# SCH_Sheet-2-more_2025-10-19.net
KiCad netlist of a schematic drawn in EasyEDA
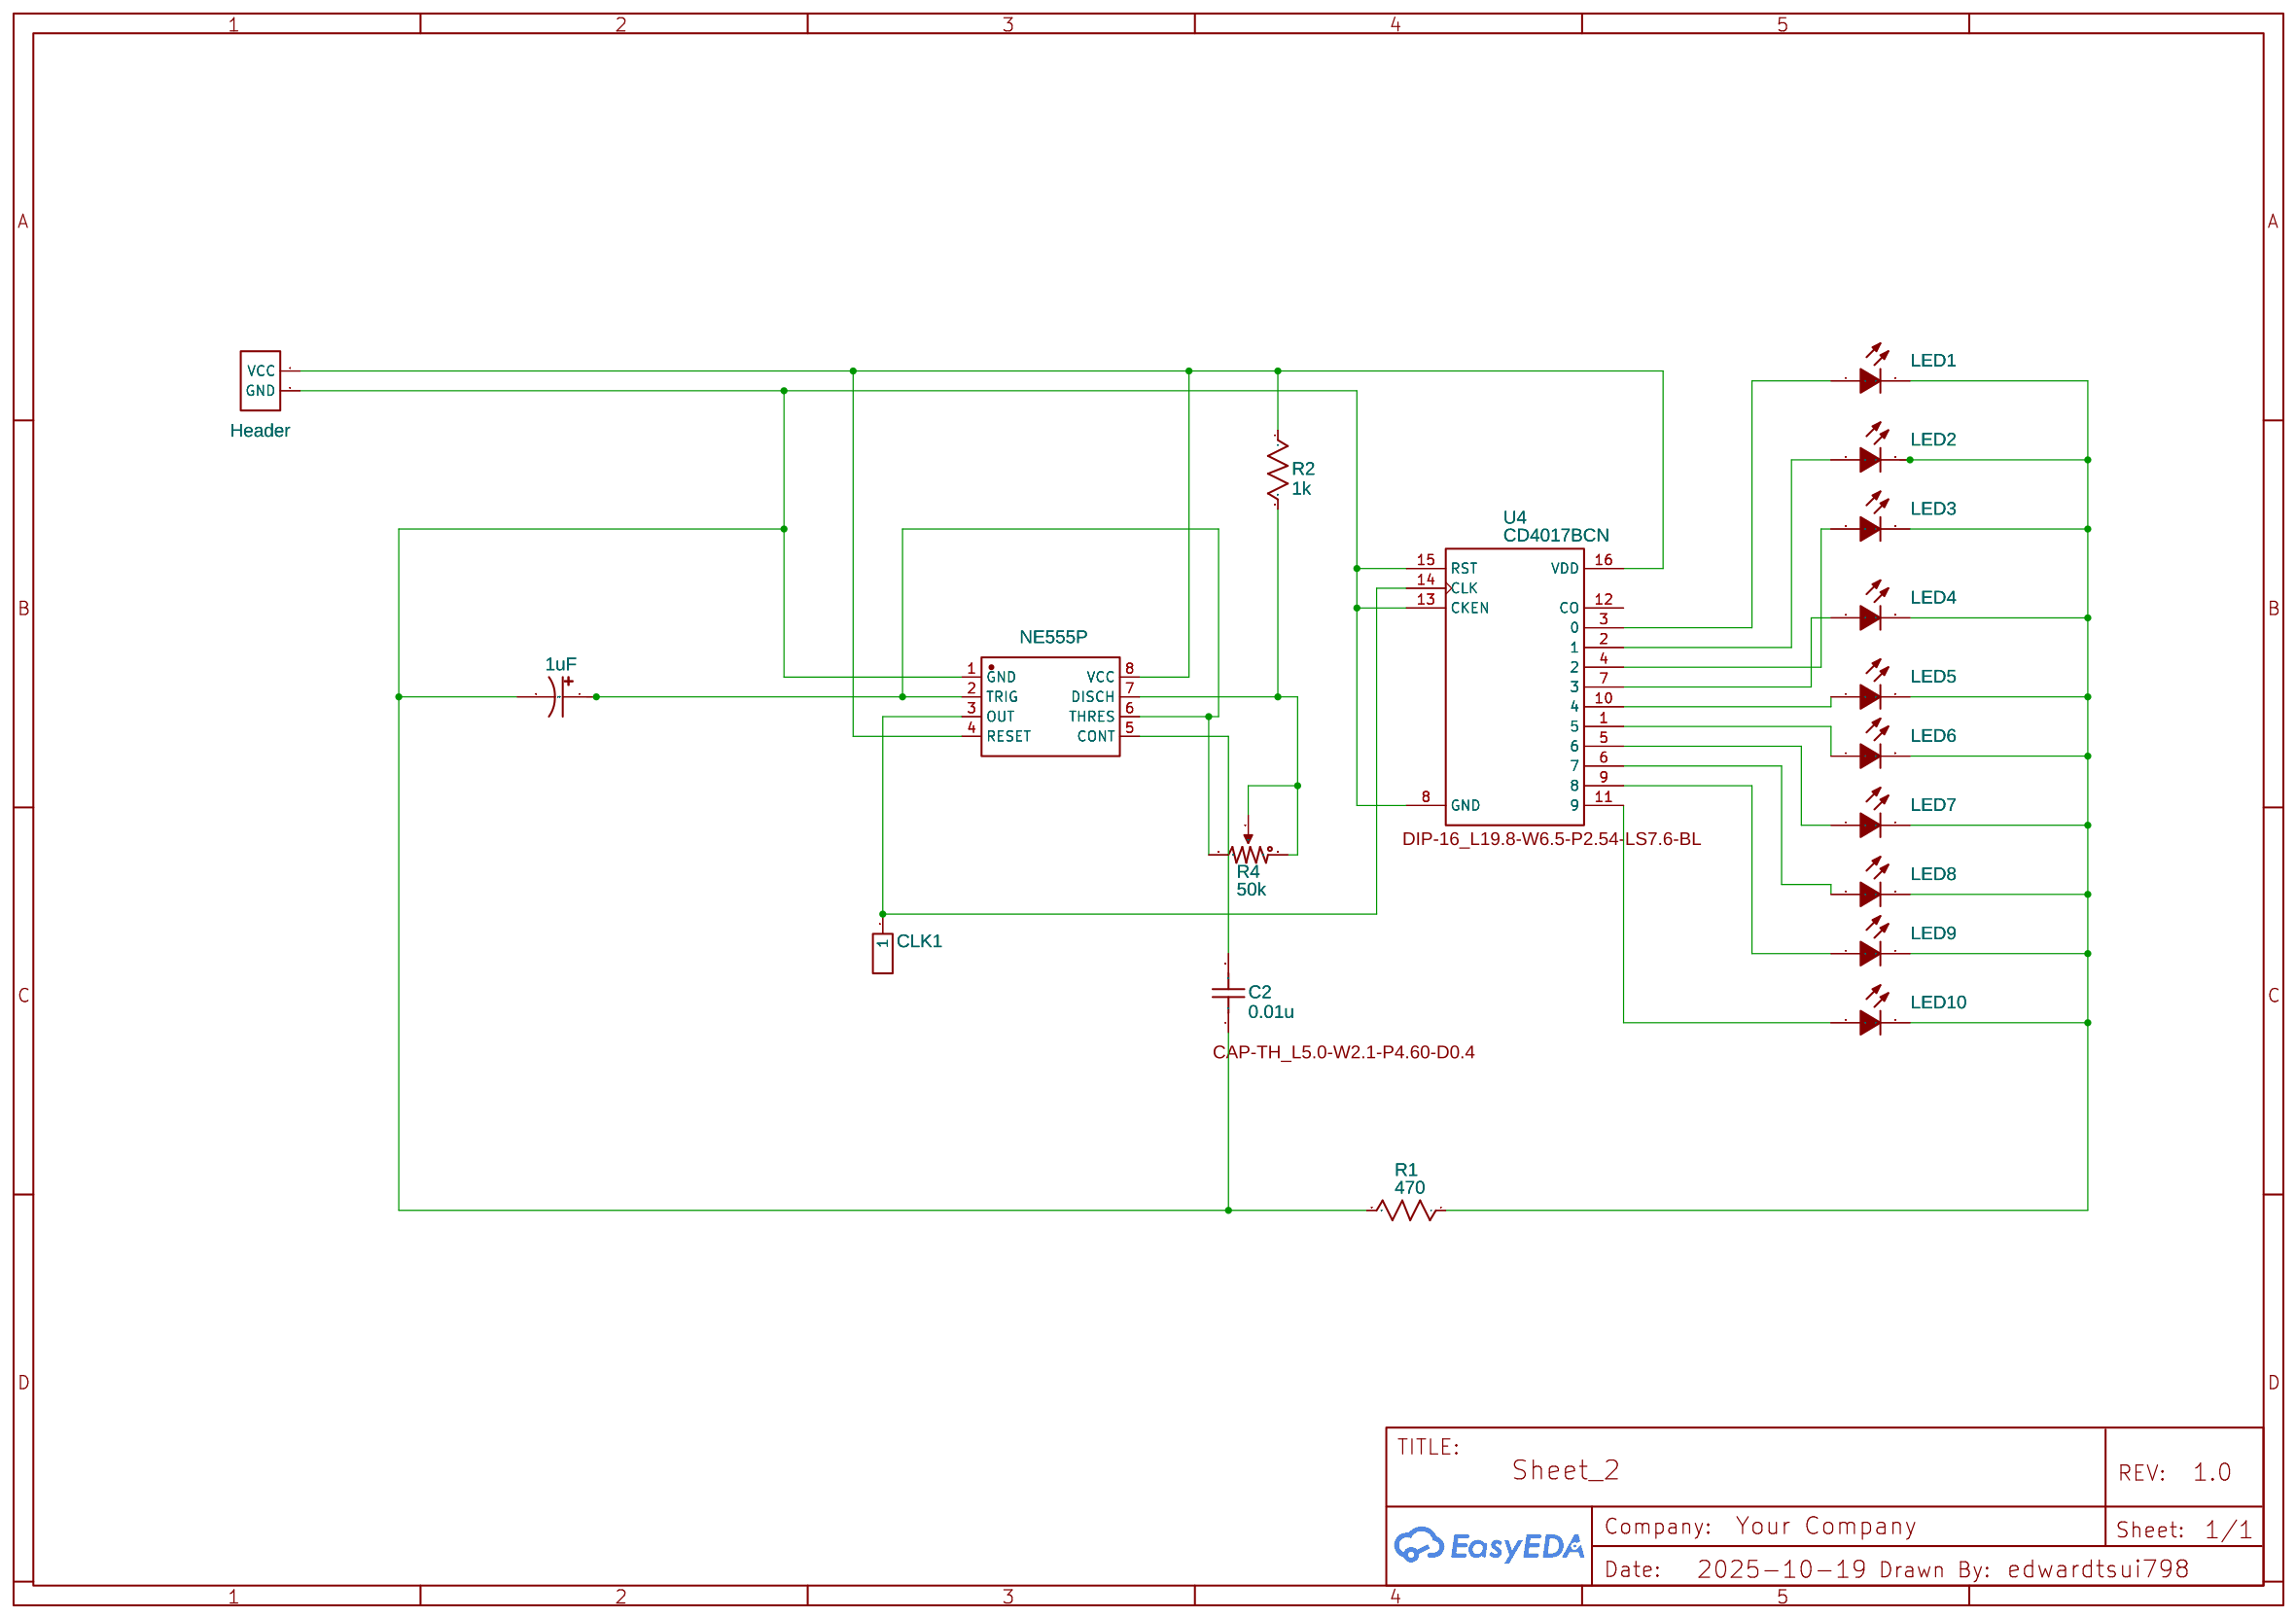
[diagram p0: schematic sheet]

(export (version "E")
  (design (tool "Eeschema 10.0.6"))
  (components
    (comp (ref "C1")
      (value "1uF")
      (fields (field (name "Manufacturer Part") "UVZ1H010MDD") (field (name "Manufacturer") "Nichicon(尼吉康)"))
      (libsource (lib "") (part "UVZ1H010MDD"))
    )
    (comp (ref "C2") (value "0.01u") (libsource (lib "") (part "C_0603_US")))
    (comp (ref "CLK1")
      (value "C81276")
      (fields
        (field (name "Manufacturer Part") "2.54-1*1P针")
        (field (name "Manufacturer") "BOOMELE(Boom Precision Elec)")
      )
      (libsource (lib "") (part "Header-Male-2.54_1x1"))
    )
    (comp (ref "H1") (value "Header") (libsource (lib "") (part "HEADER-FEMALE-2.54_1X2")))
    (comp (ref "LED1") (value "LED_5MM") (libsource (lib "") (part "LED_5MM")))
    (comp (ref "LED2") (value "LED_5MM") (libsource (lib "") (part "LED_5MM")))
    (comp (ref "LED3") (value "LED_5MM") (libsource (lib "") (part "LED_5MM")))
    (comp (ref "LED4") (value "LED_5MM") (libsource (lib "") (part "LED_5MM")))
    (comp (ref "LED5") (value "LED_5MM") (libsource (lib "") (part "LED_5MM")))
    (comp (ref "LED6") (value "LED_5MM") (libsource (lib "") (part "LED_5MM")))
    (comp (ref "LED7") (value "LED_5MM") (libsource (lib "") (part "LED_5MM")))
    (comp (ref "LED8") (value "LED_5MM") (libsource (lib "") (part "LED_5MM")))
    (comp (ref "LED9") (value "LED_5MM") (libsource (lib "") (part "LED_5MM")))
    (comp (ref "LED10") (value "LED_5MM") (libsource (lib "") (part "LED_5MM")))
    (comp (ref "R1")
      (value "470")
      (fields (field (name "Manufacturer Part") "?"))
      (libsource (lib "") (part "Resistor"))
    )
    (comp (ref "R2")
      (value "1k")
      (fields (field (name "Manufacturer Part") "?"))
      (libsource (lib "") (part "Resistor_1"))
    )
    (comp (ref "R4")
      (value "50k")
      (fields (field (name "Manufacturer Part") "?"))
      (libsource (lib "") (part "Potentiometer"))
    )
    (comp (ref "U2")
      (value "NE555P")
      (fields (field (name "Manufacturer") "TI(德州仪器)"))
      (libsource (lib "") (part "NE555P"))
    )
    (comp (ref "U4") (value "CD4017BCN") (libsource (lib "") (part "CD4017BCN")))
  )
  (nets
    (net (code "1") (name "Net-(H1-GND)") (class "Default")
      (node (ref "C1") (pin "2") (pinfunction "2_2") (pintype "unspecified"))
      (node (ref "C2") (pin "1") (pinfunction "1_1") (pintype "unspecified"))
      (node (ref "H1") (pin "2") (pinfunction "GND_2") (pintype "unspecified"))
      (node (ref "R1") (pin "2") (pinfunction "2_2") (pintype "unspecified"))
      (node (ref "U2") (pin "1") (pinfunction "GND_1") (pintype "unspecified"))
      (node (ref "U4") (pin "13") (pinfunction "CKEN_13") (pintype "unspecified"))
      (node (ref "U4") (pin "15") (pinfunction "RST_15") (pintype "unspecified"))
      (node (ref "U4") (pin "8") (pinfunction "GND_8") (pintype "passive"))
    )
    (net (code "2") (name "Net-(H1-VCC)") (class "Default")
      (node (ref "H1") (pin "1") (pinfunction "VCC_1") (pintype "unspecified"))
      (node (ref "R2") (pin "1") (pinfunction "1_1") (pintype "unspecified"))
      (node (ref "U2") (pin "4") (pinfunction "RESET_4") (pintype "unspecified"))
      (node (ref "U2") (pin "8") (pinfunction "VCC_8") (pintype "unspecified"))
      (node (ref "U4") (pin "16") (pinfunction "VDD_16") (pintype "passive"))
    )
    (net (code "3") (name "Net-(LED1-A)") (class "Default")
      (node (ref "LED1") (pin "1") (pinfunction "A_1") (pintype "input"))
      (node (ref "U4") (pin "3") (pinfunction "0_3") (pintype "output"))
    )
    (net (code "4") (name "Net-(LED1-K)") (class "Default")
      (node (ref "LED1") (pin "2") (pinfunction "K_2") (pintype "input"))
      (node (ref "LED10") (pin "2") (pinfunction "K_2") (pintype "input"))
      (node (ref "LED2") (pin "2") (pinfunction "K_2") (pintype "input"))
      (node (ref "LED3") (pin "2") (pinfunction "K_2") (pintype "input"))
      (node (ref "LED4") (pin "2") (pinfunction "K_2") (pintype "input"))
      (node (ref "LED5") (pin "2") (pinfunction "K_2") (pintype "input"))
      (node (ref "LED6") (pin "2") (pinfunction "K_2") (pintype "input"))
      (node (ref "LED7") (pin "2") (pinfunction "K_2") (pintype "input"))
      (node (ref "LED8") (pin "2") (pinfunction "K_2") (pintype "input"))
      (node (ref "LED9") (pin "2") (pinfunction "K_2") (pintype "input"))
      (node (ref "R1") (pin "1") (pinfunction "1_1") (pintype "unspecified"))
    )
    (net (code "5") (name "Net-(LED2-A)") (class "Default")
      (node (ref "LED2") (pin "1") (pinfunction "A_1") (pintype "input"))
      (node (ref "U4") (pin "2") (pinfunction "1_2") (pintype "output"))
    )
    (net (code "6") (name "Net-(LED3-A)") (class "Default")
      (node (ref "LED3") (pin "1") (pinfunction "A_1") (pintype "input"))
      (node (ref "U4") (pin "4") (pinfunction "2_4") (pintype "output"))
    )
    (net (code "7") (name "Net-(LED4-A)") (class "Default")
      (node (ref "LED4") (pin "1") (pinfunction "A_1") (pintype "input"))
      (node (ref "U4") (pin "7") (pinfunction "3_7") (pintype "output"))
    )
    (net (code "8") (name "Net-(LED5-A)") (class "Default")
      (node (ref "LED5") (pin "1") (pinfunction "A_1") (pintype "input"))
      (node (ref "U4") (pin "10") (pinfunction "4_10") (pintype "output"))
    )
    (net (code "9") (name "Net-(LED6-A)") (class "Default")
      (node (ref "LED6") (pin "1") (pinfunction "A_1") (pintype "input"))
      (node (ref "U4") (pin "1") (pinfunction "5_1") (pintype "output"))
    )
    (net (code "10") (name "Net-(LED7-A)") (class "Default")
      (node (ref "LED7") (pin "1") (pinfunction "A_1") (pintype "input"))
      (node (ref "U4") (pin "5") (pinfunction "6_5") (pintype "output"))
    )
    (net (code "11") (name "Net-(LED8-A)") (class "Default")
      (node (ref "LED8") (pin "1") (pinfunction "A_1") (pintype "input"))
      (node (ref "U4") (pin "6") (pinfunction "7_6") (pintype "output"))
    )
    (net (code "12") (name "Net-(LED9-A)") (class "Default")
      (node (ref "LED9") (pin "1") (pinfunction "A_1") (pintype "input"))
      (node (ref "U4") (pin "9") (pinfunction "8_9") (pintype "output"))
    )
    (net (code "13") (name "Net-(LED10-A)") (class "Default")
      (node (ref "LED10") (pin "1") (pinfunction "A_1") (pintype "input"))
      (node (ref "U4") (pin "11") (pinfunction "9_11") (pintype "output"))
    )
    (net (code "14") (name "Net-(R4-2)") (class "Default")
      (node (ref "R2") (pin "2") (pinfunction "2_2") (pintype "unspecified"))
      (node (ref "R4") (pin "2") (pinfunction "3_2") (pintype "unspecified"))
      (node (ref "R4") (pin "3") (pinfunction "2_3") (pintype "unspecified"))
      (node (ref "U2") (pin "7") (pinfunction "DISCH_7") (pintype "unspecified"))
    )
    (net (code "15") (name "Net-(U2-CONT)") (class "Default")
      (node (ref "C2") (pin "2") (pinfunction "2_2") (pintype "unspecified"))
      (node (ref "U2") (pin "5") (pinfunction "CONT_5") (pintype "unspecified"))
    )
    (net (code "16") (name "Net-(U2-OUT)") (class "Default")
      (node (ref "CLK1") (pin "1") (pinfunction "1_1") (pintype "unspecified"))
      (node (ref "U2") (pin "3") (pinfunction "OUT_3") (pintype "unspecified"))
      (node (ref "U4") (pin "14") (pinfunction "CLK_14") (pintype "unspecified"))
    )
    (net (code "17") (name "Net-(U2-THRES)") (class "Default")
      (node (ref "C1") (pin "1") (pinfunction "1_1") (pintype "unspecified"))
      (node (ref "R4") (pin "1") (pinfunction "1_1") (pintype "unspecified"))
      (node (ref "U2") (pin "2") (pinfunction "TRIG_2") (pintype "unspecified"))
      (node (ref "U2") (pin "6") (pinfunction "THRES_6") (pintype "unspecified"))
    )
    (net (code "18") (name "unconnected-(U4-CO-Pad12)") (class "Default")
      (node (ref "U4") (pin "12") (pinfunction "CO_12") (pintype "output"))
    )
  )
)
